# Dual_opto_input.net
KiCad netlist of a schematic drawn in Altium Designer
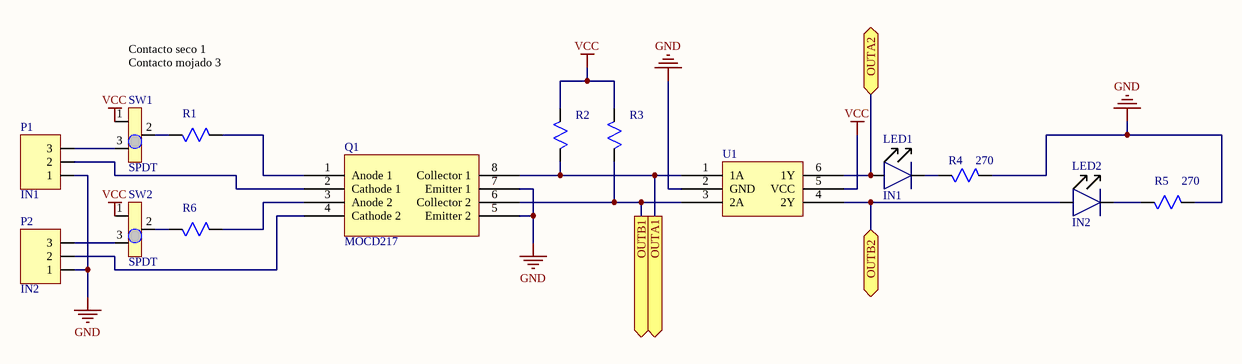
[diagram p0: Dual_opto_input.SchDoc]

(export (version "E")
  (design (tool "Eeschema 10.0.6"))
  (components
    (comp (ref "LED1")
      (value "IN1")
      (footprint "SMD1206")
      (description "Discrete Led SMD")
      (fields
        (field (name "DIGI-KEY PART NUMBER") "160-1169-1-ND")
        (field (name "MANUFACTURERS PART NUMBER") "LTST-C150GKT")
      )
      (libsource (lib "PAT_Library") (part "LedSMD"))
    )
    (comp (ref "LED2")
      (value "IN2")
      (footprint "SMD1206")
      (description "Discrete Led SMD")
      (fields
        (field (name "DIGI-KEY PART NUMBER") "160-1169-1-ND")
        (field (name "MANUFACTURERS PART NUMBER") "LTST-C150GKT")
      )
      (libsource (lib "PAT_Library") (part "LedSMD"))
    )
    (comp (ref "P1")
      (value "IN1")
      (footprint "TBHDR3P3.5")
      (description "Connector 3 positions with pitch 3.5mm")
      (fields
        (field (name "DIGI-KEY PART NUMBER") "277-11008-ND")
        (field (name "MANUFACTURERS PART NUMBER") "1897102")
      )
      (libsource (lib "PAT Connectors Board") (part "TBHDR3P3.5"))
    )
    (comp (ref "P2")
      (value "IN2")
      (footprint "TBHDR3P3.5")
      (description "Connector 3 positions with pitch 3.5mm")
      (fields
        (field (name "DIGI-KEY PART NUMBER") "277-11008-ND")
        (field (name "MANUFACTURERS PART NUMBER") "1897102")
      )
      (libsource (lib "PAT Connectors Board") (part "TBHDR3P3.5"))
    )
    (comp (ref "Q1")
      (value "MOCD217")
      (footprint "SOIC8")
      (description "Optocoupler")
      (fields
        (field (name "DIGI-KEY PART NUMBER") "MOCD217R2MCT-ND")
        (field (name "MANUFACTURERS PART NUMBER") "MOCD217R2M")
      )
      (libsource (lib "PAT_Library") (part "MOCD217"))
    )
    (comp (ref "R1")
      (value "~")
      (footprint "ResistorSMD0805")
      (description "Chip Resistor SMD")
      (fields
        (field (name "DIGI-KEY PART NUMBER") "311-680CRCT-ND")
        (field (name "MANUFACTURERS PART NUMBER") "RC0805FR-07680RL")
      )
      (libsource (lib "PAT_Library") (part "ResistorSMD"))
    )
    (comp (ref "R2")
      (value "~")
      (footprint "ResistorSMD0805")
      (description "Chip Resistor SMD")
      (fields
        (field (name "DIGI-KEY PART NUMBER") "311-680CRCT-ND")
        (field (name "MANUFACTURERS PART NUMBER") "RC0805FR-07680RL")
      )
      (libsource (lib "PAT_Library") (part "ResistorSMD"))
    )
    (comp (ref "R3")
      (value "~")
      (footprint "ResistorSMD0805")
      (description "Chip Resistor SMD")
      (fields
        (field (name "DIGI-KEY PART NUMBER") "311-680CRCT-ND")
        (field (name "MANUFACTURERS PART NUMBER") "RC0805FR-07680RL")
      )
      (libsource (lib "PAT_Library") (part "ResistorSMD"))
    )
    (comp (ref "R4")
      (value "270")
      (footprint "ResistorSMD0805")
      (description "Chip Resistor SMD")
      (fields
        (field (name "DIGI-KEY PART NUMBER") "YAG3714CT-ND")
        (field (name "MANUFACTURERS PART NUMBER") "AC0805FR-07270RL")
      )
      (libsource (lib "PAT_Library") (part "ResistorSMD"))
    )
    (comp (ref "R5")
      (value "270")
      (footprint "ResistorSMD0805")
      (description "Chip Resistor SMD")
      (fields
        (field (name "DIGI-KEY PART NUMBER") "YAG3714CT-ND")
        (field (name "MANUFACTURERS PART NUMBER") "AC0805FR-07270RL")
      )
      (libsource (lib "PAT_Library") (part "ResistorSMD"))
    )
    (comp (ref "R6")
      (value "~")
      (footprint "ResistorSMD0805")
      (description "Chip Resistor SMD")
      (fields
        (field (name "DIGI-KEY PART NUMBER") "311-680CRCT-ND")
        (field (name "MANUFACTURERS PART NUMBER") "RC0805FR-07680RL")
      )
      (libsource (lib "PAT_Library") (part "ResistorSMD"))
    )
    (comp (ref "SW1")
      (value "SPDT")
      (footprint "SPDT SMD")
      (description "200mA 12V")
      (fields
        (field (name "DIGI-KEY PART NUMBER") "563-1318-1-ND")
        (field (name "MANUFACTURERS PART NUMBER") "CL-SB-12B-01T")
      )
      (libsource (lib "PAT_Library") (part "SW_SPDT"))
    )
    (comp (ref "SW2")
      (value "SPDT")
      (footprint "SPDT SMD")
      (description "200mA 12V")
      (fields
        (field (name "DIGI-KEY PART NUMBER") "563-1318-1-ND")
        (field (name "MANUFACTURERS PART NUMBER") "CL-SB-12B-01T")
      )
      (libsource (lib "PAT_Library") (part "SW_SPDT"))
    )
    (comp (ref "U1")
      (value "Inverter2x2")
      (footprint "Inverter2x2")
      (description "Logic Inverter 2 Circuits")
      (fields
        (field (name "DIGI-KEY PART NUMBER") "296-27361-1-ND")
        (field (name "MANUFACTURERS PART NUMBER") "SN74AUP2G14DCKR")
      )
      (libsource (lib "PAT_Library") (part "Inverter2x2"))
    )
  )
  (nets
    (net (code "1") (name "/OUTA1") (class "Default")
      (node (ref "Q1") (pin "8") (pinfunction "Collector_1_8") (pintype "passive"))
      (node (ref "R2") (pin "2") (pinfunction "2_2") (pintype "passive"))
      (node (ref "U1") (pin "1") (pinfunction "1A_1") (pintype "passive"))
    )
    (net (code "2") (name "/OUTA2") (class "Default")
      (node (ref "LED1") (pin "2") (pinfunction "2_2") (pintype "passive"))
      (node (ref "U1") (pin "6") (pinfunction "1Y_6") (pintype "passive"))
    )
    (net (code "3") (name "/OUTB1") (class "Default")
      (node (ref "Q1") (pin "6") (pinfunction "Collector_2_6") (pintype "passive"))
      (node (ref "R3") (pin "2") (pinfunction "2_2") (pintype "passive"))
      (node (ref "U1") (pin "3") (pinfunction "2A_3") (pintype "passive"))
    )
    (net (code "4") (name "/OUTB2") (class "Default")
      (node (ref "LED2") (pin "2") (pinfunction "2_2") (pintype "passive"))
      (node (ref "U1") (pin "4") (pinfunction "2Y_4") (pintype "passive"))
    )
    (net (code "5") (name "GND") (class "Default")
      (node (ref "P1") (pin "1") (pinfunction "1_1") (pintype "passive"))
      (node (ref "P2") (pin "1") (pinfunction "1_1") (pintype "passive"))
      (node (ref "Q1") (pin "5") (pinfunction "Emitter_2_5") (pintype "passive"))
      (node (ref "Q1") (pin "7") (pinfunction "Emitter_1_7") (pintype "passive"))
      (node (ref "R4") (pin "1") (pinfunction "1_1") (pintype "passive"))
      (node (ref "R5") (pin "1") (pinfunction "1_1") (pintype "passive"))
      (node (ref "U1") (pin "2") (pinfunction "GND_2") (pintype "passive"))
    )
    (net (code "6") (name "Net-(LED1-Pad1)") (class "Default")
      (node (ref "LED1") (pin "1") (pinfunction "1_1") (pintype "passive"))
      (node (ref "R4") (pin "2") (pinfunction "2_2") (pintype "passive"))
    )
    (net (code "7") (name "Net-(LED2-Pad1)") (class "Default")
      (node (ref "LED2") (pin "1") (pinfunction "1_1") (pintype "passive"))
      (node (ref "R5") (pin "2") (pinfunction "2_2") (pintype "passive"))
    )
    (net (code "8") (name "Net-(P1-Pad3)") (class "Default")
      (node (ref "P1") (pin "3") (pinfunction "3_3") (pintype "passive"))
      (node (ref "SW1") (pin "3") (pintype "passive"))
    )
    (net (code "9") (name "Net-(P2-Pad3)") (class "Default")
      (node (ref "P2") (pin "3") (pinfunction "3_3") (pintype "passive"))
      (node (ref "SW2") (pin "3") (pintype "passive"))
    )
    (net (code "10") (name "Net-(Q1-Anode_1)") (class "Default")
      (node (ref "Q1") (pin "1") (pinfunction "Anode_1_1") (pintype "passive"))
      (node (ref "R1") (pin "1") (pinfunction "1_1") (pintype "passive"))
    )
    (net (code "11") (name "Net-(Q1-Anode_2)") (class "Default")
      (node (ref "Q1") (pin "3") (pinfunction "Anode_2_3") (pintype "passive"))
      (node (ref "R6") (pin "1") (pinfunction "1_1") (pintype "passive"))
    )
    (net (code "12") (name "Net-(Q1-Cathode_1)") (class "Default")
      (node (ref "P1") (pin "2") (pinfunction "2_2") (pintype "passive"))
      (node (ref "Q1") (pin "2") (pinfunction "Cathode_1_2") (pintype "passive"))
    )
    (net (code "13") (name "Net-(Q1-Cathode_2)") (class "Default")
      (node (ref "P2") (pin "2") (pinfunction "2_2") (pintype "passive"))
      (node (ref "Q1") (pin "4") (pinfunction "Cathode_2_4") (pintype "passive"))
    )
    (net (code "14") (name "Net-(R1-Pad2)") (class "Default")
      (node (ref "R1") (pin "2") (pinfunction "2_2") (pintype "passive"))
      (node (ref "SW1") (pin "2") (pintype "passive"))
    )
    (net (code "15") (name "Net-(R6-Pad2)") (class "Default")
      (node (ref "R6") (pin "2") (pinfunction "2_2") (pintype "passive"))
      (node (ref "SW2") (pin "2") (pintype "passive"))
    )
    (net (code "16") (name "VCC") (class "Default")
      (node (ref "R2") (pin "1") (pinfunction "1_1") (pintype "passive"))
      (node (ref "R3") (pin "1") (pinfunction "1_1") (pintype "passive"))
      (node (ref "SW1") (pin "1") (pintype "passive"))
      (node (ref "SW2") (pin "1") (pintype "passive"))
      (node (ref "U1") (pin "5") (pinfunction "VCC_5") (pintype "passive"))
    )
  )
)
